# piHatMotorDriver.net
KiCad netlist of a schematic drawn in EAGLE
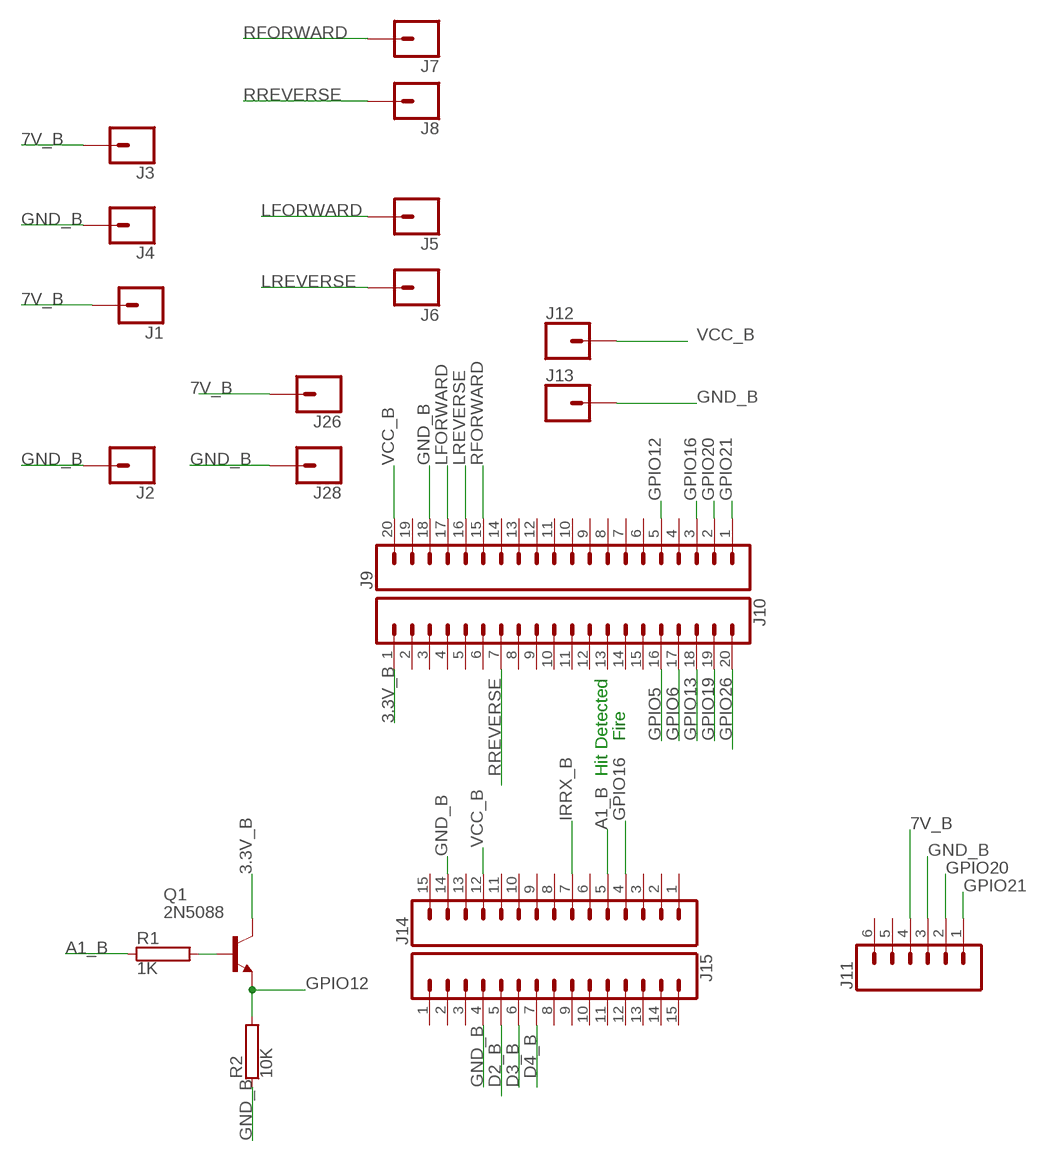
[diagram p0: schematic, sheet 1]

(export (version "E")
  (design (tool "Eeschema 10.0.6"))
  (components
    (comp (ref "J1")
      (value "CONN_01")
      (footprint "eagle-import:1X01")
      (libsource (lib "eagle-import") (part "CONN_01"))
    )
    (comp (ref "J2")
      (value "CONN_01")
      (footprint "eagle-import:1X01")
      (libsource (lib "eagle-import") (part "CONN_01"))
    )
    (comp (ref "J3")
      (value "CONN_01")
      (footprint "eagle-import:1X01")
      (libsource (lib "eagle-import") (part "CONN_01"))
    )
    (comp (ref "J4")
      (value "CONN_01")
      (footprint "eagle-import:1X01")
      (libsource (lib "eagle-import") (part "CONN_01"))
    )
    (comp (ref "J5")
      (value "CONN_01")
      (footprint "eagle-import:1X01")
      (libsource (lib "eagle-import") (part "CONN_01"))
    )
    (comp (ref "J6")
      (value "CONN_01")
      (footprint "eagle-import:1X01")
      (libsource (lib "eagle-import") (part "CONN_01"))
    )
    (comp (ref "J7")
      (value "CONN_01")
      (footprint "eagle-import:1X01")
      (libsource (lib "eagle-import") (part "CONN_01"))
    )
    (comp (ref "J8")
      (value "CONN_01")
      (footprint "eagle-import:1X01")
      (libsource (lib "eagle-import") (part "CONN_01"))
    )
    (comp (ref "J9")
      (value "CONN_20")
      (footprint "eagle-import:1X20")
      (libsource (lib "eagle-import") (part "CONN_20"))
    )
    (comp (ref "J10")
      (value "CONN_20")
      (footprint "eagle-import:1X20")
      (libsource (lib "eagle-import") (part "CONN_20"))
    )
    (comp (ref "J11")
      (value "CONN_06SILK_FEMALE_PTH")
      (footprint "eagle-import:1X06")
      (libsource (lib "eagle-import") (part "CONN_06SILK_FEMALE_PTH"))
    )
    (comp (ref "J12")
      (value "CONN_01")
      (footprint "eagle-import:1X01")
      (libsource (lib "eagle-import") (part "CONN_01"))
    )
    (comp (ref "J13")
      (value "CONN_01")
      (footprint "eagle-import:1X01")
      (libsource (lib "eagle-import") (part "CONN_01"))
    )
    (comp (ref "J14")
      (value "CONN_15")
      (footprint "eagle-import:1X15")
      (libsource (lib "eagle-import") (part "CONN_15"))
    )
    (comp (ref "J15")
      (value "CONN_15")
      (footprint "eagle-import:1X15")
      (libsource (lib "eagle-import") (part "CONN_15"))
    )
    (comp (ref "J26")
      (value "CONN_01")
      (footprint "eagle-import:1X01")
      (libsource (lib "eagle-import") (part "CONN_01"))
    )
    (comp (ref "J28")
      (value "CONN_01")
      (footprint "eagle-import:1X01")
      (libsource (lib "eagle-import") (part "CONN_01"))
    )
    (comp (ref "Q1")
      (value "2N5088")
      (footprint "eagle-import:TO92")
      (libsource (lib "eagle-import") (part "2N5088"))
    )
    (comp (ref "R1")
      (value "1K")
      (footprint "eagle-import:CA0001")
      (libsource (lib "eagle-import") (part "RCA0001"))
    )
    (comp (ref "R2")
      (value "10K")
      (footprint "eagle-import:CA0001")
      (libsource (lib "eagle-import") (part "RCA0001"))
    )
  )
  (nets
    (net (code "1") (name "/3.3V_B") (class "Default")
      (node (ref "J10") (pin "1") (pinfunction "1_1") (pintype "passive"))
      (node (ref "Q1") (pin "1") (pinfunction "C_1") (pintype "passive"))
    )
    (net (code "2") (name "/7V_B") (class "Default")
      (node (ref "J1") (pin "1") (pinfunction "1_1") (pintype "passive"))
      (node (ref "J11") (pin "4") (pinfunction "4_4") (pintype "passive"))
      (node (ref "J26") (pin "1") (pinfunction "1_1") (pintype "passive"))
      (node (ref "J3") (pin "1") (pinfunction "1_1") (pintype "passive"))
    )
    (net (code "3") (name "/A1_B") (class "Default")
      (node (ref "J14") (pin "5") (pinfunction "5_5") (pintype "passive"))
      (node (ref "R1") (pin "1") (pinfunction "1_1") (pintype "passive"))
    )
    (net (code "4") (name "/D2_B") (class "Default")
      (node (ref "J15") (pin "5") (pinfunction "5_5") (pintype "passive"))
    )
    (net (code "5") (name "/D3_B") (class "Default")
      (node (ref "J15") (pin "6") (pinfunction "6_6") (pintype "passive"))
    )
    (net (code "6") (name "/D4_B") (class "Default")
      (node (ref "J15") (pin "7") (pinfunction "7_7") (pintype "passive"))
    )
    (net (code "7") (name "/GND_B") (class "Default")
      (node (ref "J11") (pin "3") (pinfunction "3_3") (pintype "passive"))
      (node (ref "J13") (pin "1") (pinfunction "1_1") (pintype "passive"))
      (node (ref "J14") (pin "14") (pinfunction "14_14") (pintype "passive"))
      (node (ref "J15") (pin "4") (pinfunction "4_4") (pintype "passive"))
      (node (ref "J2") (pin "1") (pinfunction "1_1") (pintype "passive"))
      (node (ref "J28") (pin "1") (pinfunction "1_1") (pintype "passive"))
      (node (ref "J4") (pin "1") (pinfunction "1_1") (pintype "passive"))
      (node (ref "J9") (pin "18") (pinfunction "18_18") (pintype "passive"))
      (node (ref "R2") (pin "1") (pinfunction "1_1") (pintype "passive"))
    )
    (net (code "8") (name "/GPIO5") (class "Default")
      (node (ref "J10") (pin "16") (pinfunction "16_16") (pintype "passive"))
    )
    (net (code "9") (name "/GPIO6") (class "Default")
      (node (ref "J10") (pin "17") (pinfunction "17_17") (pintype "passive"))
    )
    (net (code "10") (name "/GPIO12") (class "Default")
      (node (ref "J9") (pin "5") (pinfunction "5_5") (pintype "passive"))
      (node (ref "Q1") (pin "3") (pinfunction "E_3") (pintype "passive"))
      (node (ref "R2") (pin "2") (pinfunction "2_2") (pintype "passive"))
    )
    (net (code "11") (name "/GPIO13") (class "Default")
      (node (ref "J10") (pin "18") (pinfunction "18_18") (pintype "passive"))
    )
    (net (code "12") (name "/GPIO16") (class "Default")
      (node (ref "J14") (pin "4") (pinfunction "4_4") (pintype "passive"))
      (node (ref "J9") (pin "3") (pinfunction "3_3") (pintype "passive"))
    )
    (net (code "13") (name "/GPIO19") (class "Default")
      (node (ref "J10") (pin "19") (pinfunction "19_19") (pintype "passive"))
    )
    (net (code "14") (name "/GPIO20") (class "Default")
      (node (ref "J11") (pin "2") (pinfunction "2_2") (pintype "passive"))
      (node (ref "J9") (pin "2") (pinfunction "2_2") (pintype "passive"))
    )
    (net (code "15") (name "/GPIO21") (class "Default")
      (node (ref "J11") (pin "1") (pinfunction "1_1") (pintype "passive"))
      (node (ref "J9") (pin "1") (pinfunction "1_1") (pintype "passive"))
    )
    (net (code "16") (name "/GPIO26") (class "Default")
      (node (ref "J10") (pin "20") (pinfunction "20_20") (pintype "passive"))
    )
    (net (code "17") (name "/IRRX_B") (class "Default")
      (node (ref "J14") (pin "7") (pinfunction "7_7") (pintype "passive"))
    )
    (net (code "18") (name "/LFORWARD") (class "Default")
      (node (ref "J5") (pin "1") (pinfunction "1_1") (pintype "passive"))
      (node (ref "J9") (pin "17") (pinfunction "17_17") (pintype "passive"))
    )
    (net (code "19") (name "/LREVERSE") (class "Default")
      (node (ref "J6") (pin "1") (pinfunction "1_1") (pintype "passive"))
      (node (ref "J9") (pin "16") (pinfunction "16_16") (pintype "passive"))
    )
    (net (code "20") (name "/RFORWARD") (class "Default")
      (node (ref "J7") (pin "1") (pinfunction "1_1") (pintype "passive"))
      (node (ref "J9") (pin "15") (pinfunction "15_15") (pintype "passive"))
    )
    (net (code "21") (name "/RREVERSE") (class "Default")
      (node (ref "J10") (pin "7") (pinfunction "7_7") (pintype "passive"))
      (node (ref "J8") (pin "1") (pinfunction "1_1") (pintype "passive"))
    )
    (net (code "22") (name "/VCC_B") (class "Default")
      (node (ref "J12") (pin "1") (pinfunction "1_1") (pintype "passive"))
      (node (ref "J14") (pin "12") (pinfunction "12_12") (pintype "passive"))
      (node (ref "J9") (pin "20") (pinfunction "20_20") (pintype "passive"))
    )
    (net (code "23") (name "Net-(Q1-B)") (class "Default")
      (node (ref "Q1") (pin "2") (pinfunction "B_2") (pintype "passive"))
      (node (ref "R1") (pin "2") (pinfunction "2_2") (pintype "passive"))
    )
    (net (code "24") (name "unconnected-(J9-Pad4)") (class "Default")
      (node (ref "J9") (pin "4") (pinfunction "4_4") (pintype "passive"))
    )
    (net (code "25") (name "unconnected-(J9-Pad6)") (class "Default")
      (node (ref "J9") (pin "6") (pinfunction "6_6") (pintype "passive"))
    )
    (net (code "26") (name "unconnected-(J9-Pad7)") (class "Default")
      (node (ref "J9") (pin "7") (pinfunction "7_7") (pintype "passive"))
    )
    (net (code "27") (name "unconnected-(J9-Pad8)") (class "Default")
      (node (ref "J9") (pin "8") (pinfunction "8_8") (pintype "passive"))
    )
    (net (code "28") (name "unconnected-(J9-Pad9)") (class "Default")
      (node (ref "J9") (pin "9") (pinfunction "9_9") (pintype "passive"))
    )
    (net (code "29") (name "unconnected-(J9-Pad10)") (class "Default")
      (node (ref "J9") (pin "10") (pinfunction "10_10") (pintype "passive"))
    )
    (net (code "30") (name "unconnected-(J9-Pad11)") (class "Default")
      (node (ref "J9") (pin "11") (pinfunction "11_11") (pintype "passive"))
    )
    (net (code "31") (name "unconnected-(J9-Pad12)") (class "Default")
      (node (ref "J9") (pin "12") (pinfunction "12_12") (pintype "passive"))
    )
    (net (code "32") (name "unconnected-(J9-Pad13)") (class "Default")
      (node (ref "J9") (pin "13") (pinfunction "13_13") (pintype "passive"))
    )
    (net (code "33") (name "unconnected-(J9-Pad14)") (class "Default")
      (node (ref "J9") (pin "14") (pinfunction "14_14") (pintype "passive"))
    )
    (net (code "34") (name "unconnected-(J9-Pad19)") (class "Default")
      (node (ref "J9") (pin "19") (pinfunction "19_19") (pintype "passive"))
    )
    (net (code "35") (name "unconnected-(J10-Pad2)") (class "Default")
      (node (ref "J10") (pin "2") (pinfunction "2_2") (pintype "passive"))
    )
    (net (code "36") (name "unconnected-(J10-Pad3)") (class "Default")
      (node (ref "J10") (pin "3") (pinfunction "3_3") (pintype "passive"))
    )
    (net (code "37") (name "unconnected-(J10-Pad4)") (class "Default")
      (node (ref "J10") (pin "4") (pinfunction "4_4") (pintype "passive"))
    )
    (net (code "38") (name "unconnected-(J10-Pad5)") (class "Default")
      (node (ref "J10") (pin "5") (pinfunction "5_5") (pintype "passive"))
    )
    (net (code "39") (name "unconnected-(J10-Pad6)") (class "Default")
      (node (ref "J10") (pin "6") (pinfunction "6_6") (pintype "passive"))
    )
    (net (code "40") (name "unconnected-(J10-Pad8)") (class "Default")
      (node (ref "J10") (pin "8") (pinfunction "8_8") (pintype "passive"))
    )
    (net (code "41") (name "unconnected-(J10-Pad9)") (class "Default")
      (node (ref "J10") (pin "9") (pinfunction "9_9") (pintype "passive"))
    )
    (net (code "42") (name "unconnected-(J10-Pad10)") (class "Default")
      (node (ref "J10") (pin "10") (pinfunction "10_10") (pintype "passive"))
    )
    (net (code "43") (name "unconnected-(J10-Pad11)") (class "Default")
      (node (ref "J10") (pin "11") (pinfunction "11_11") (pintype "passive"))
    )
    (net (code "44") (name "unconnected-(J10-Pad12)") (class "Default")
      (node (ref "J10") (pin "12") (pinfunction "12_12") (pintype "passive"))
    )
    (net (code "45") (name "unconnected-(J10-Pad13)") (class "Default")
      (node (ref "J10") (pin "13") (pinfunction "13_13") (pintype "passive"))
    )
    (net (code "46") (name "unconnected-(J10-Pad14)") (class "Default")
      (node (ref "J10") (pin "14") (pinfunction "14_14") (pintype "passive"))
    )
    (net (code "47") (name "unconnected-(J10-Pad15)") (class "Default")
      (node (ref "J10") (pin "15") (pinfunction "15_15") (pintype "passive"))
    )
    (net (code "48") (name "unconnected-(J11-Pad5)") (class "Default")
      (node (ref "J11") (pin "5") (pinfunction "5_5") (pintype "passive"))
    )
    (net (code "49") (name "unconnected-(J11-Pad6)") (class "Default")
      (node (ref "J11") (pin "6") (pinfunction "6_6") (pintype "passive"))
    )
    (net (code "50") (name "unconnected-(J14-Pad1)") (class "Default")
      (node (ref "J14") (pin "1") (pinfunction "1_1") (pintype "passive"))
    )
    (net (code "51") (name "unconnected-(J14-Pad2)") (class "Default")
      (node (ref "J14") (pin "2") (pinfunction "2_2") (pintype "passive"))
    )
    (net (code "52") (name "unconnected-(J14-Pad3)") (class "Default")
      (node (ref "J14") (pin "3") (pinfunction "3_3") (pintype "passive"))
    )
    (net (code "53") (name "unconnected-(J14-Pad6)") (class "Default")
      (node (ref "J14") (pin "6") (pinfunction "6_6") (pintype "passive"))
    )
    (net (code "54") (name "unconnected-(J14-Pad8)") (class "Default")
      (node (ref "J14") (pin "8") (pinfunction "8_8") (pintype "passive"))
    )
    (net (code "55") (name "unconnected-(J14-Pad9)") (class "Default")
      (node (ref "J14") (pin "9") (pinfunction "9_9") (pintype "passive"))
    )
    (net (code "56") (name "unconnected-(J14-Pad10)") (class "Default")
      (node (ref "J14") (pin "10") (pinfunction "10_10") (pintype "passive"))
    )
    (net (code "57") (name "unconnected-(J14-Pad11)") (class "Default")
      (node (ref "J14") (pin "11") (pinfunction "11_11") (pintype "passive"))
    )
    (net (code "58") (name "unconnected-(J14-Pad13)") (class "Default")
      (node (ref "J14") (pin "13") (pinfunction "13_13") (pintype "passive"))
    )
    (net (code "59") (name "unconnected-(J14-Pad15)") (class "Default")
      (node (ref "J14") (pin "15") (pinfunction "15_15") (pintype "passive"))
    )
    (net (code "60") (name "unconnected-(J15-Pad1)") (class "Default")
      (node (ref "J15") (pin "1") (pinfunction "1_1") (pintype "passive"))
    )
    (net (code "61") (name "unconnected-(J15-Pad2)") (class "Default")
      (node (ref "J15") (pin "2") (pinfunction "2_2") (pintype "passive"))
    )
    (net (code "62") (name "unconnected-(J15-Pad3)") (class "Default")
      (node (ref "J15") (pin "3") (pinfunction "3_3") (pintype "passive"))
    )
    (net (code "63") (name "unconnected-(J15-Pad8)") (class "Default")
      (node (ref "J15") (pin "8") (pinfunction "8_8") (pintype "passive"))
    )
    (net (code "64") (name "unconnected-(J15-Pad9)") (class "Default")
      (node (ref "J15") (pin "9") (pinfunction "9_9") (pintype "passive"))
    )
    (net (code "65") (name "unconnected-(J15-Pad10)") (class "Default")
      (node (ref "J15") (pin "10") (pinfunction "10_10") (pintype "passive"))
    )
    (net (code "66") (name "unconnected-(J15-Pad11)") (class "Default")
      (node (ref "J15") (pin "11") (pinfunction "11_11") (pintype "passive"))
    )
    (net (code "67") (name "unconnected-(J15-Pad12)") (class "Default")
      (node (ref "J15") (pin "12") (pinfunction "12_12") (pintype "passive"))
    )
    (net (code "68") (name "unconnected-(J15-Pad13)") (class "Default")
      (node (ref "J15") (pin "13") (pinfunction "13_13") (pintype "passive"))
    )
    (net (code "69") (name "unconnected-(J15-Pad14)") (class "Default")
      (node (ref "J15") (pin "14") (pinfunction "14_14") (pintype "passive"))
    )
    (net (code "70") (name "unconnected-(J15-Pad15)") (class "Default")
      (node (ref "J15") (pin "15") (pinfunction "15_15") (pintype "passive"))
    )
  )
)
